# connections.net
KiCad netlist of a schematic drawn in EAGLE
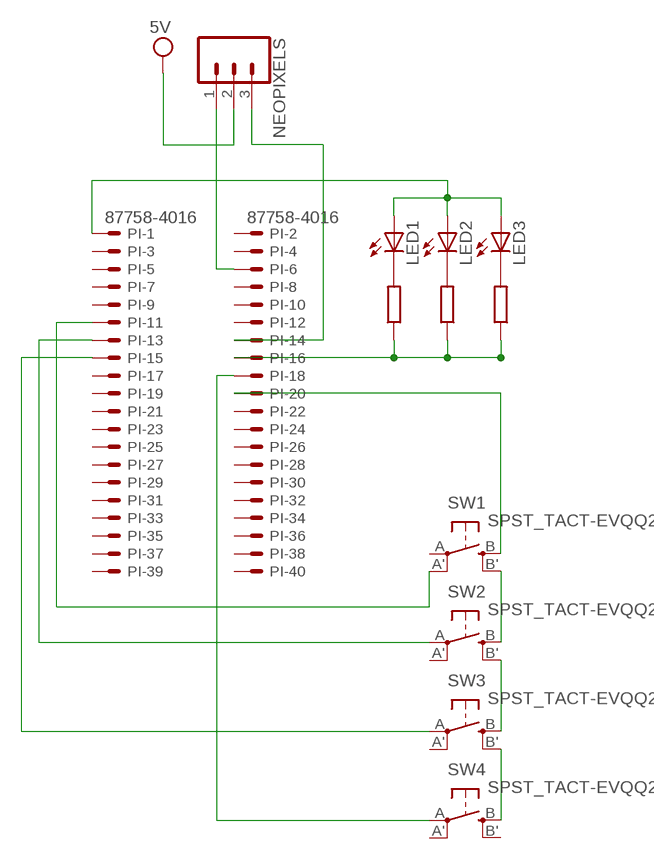
[diagram p0: schematic, sheet 1]

(export (version "E")
  (design (tool "Eeschema 10.0.6"))
  (components
    (comp (ref "LED1")
      (value "LED3MM")
      (footprint "eagle-import:LED3MM")
      (libsource (lib "eagle-import") (part "LED3MM"))
    )
    (comp (ref "LED2")
      (value "LED3MM")
      (footprint "eagle-import:LED3MM")
      (libsource (lib "eagle-import") (part "LED3MM"))
    )
    (comp (ref "LED3")
      (value "LED3MM")
      (footprint "eagle-import:LED3MM")
      (libsource (lib "eagle-import") (part "LED3MM"))
    )
    (comp (ref "NEOPIXELS")
      (value "CONN_031X03_NO_SILK")
      (footprint "eagle-import:1X03_NO_SILK")
      (libsource (lib "eagle-import") (part "CONN_031X03_NO_SILK"))
    )
    (comp (ref "PI")
      (value "87758-4016")
      (footprint "eagle-import:87758-4016")
      (fields (field (name "MF") "MOLEX"))
      (libsource (lib "eagle-import") (part "87758-4016"))
    )
    (comp (ref "SW1")
      (value "SPST_TACT-EVQQ2")
      (footprint "eagle-import:EVQ-Q2")
      (libsource (lib "eagle-import") (part "SPST_TACT-EVQQ2"))
    )
    (comp (ref "SW2")
      (value "SPST_TACT-EVQQ2")
      (footprint "eagle-import:EVQ-Q2")
      (libsource (lib "eagle-import") (part "SPST_TACT-EVQQ2"))
    )
    (comp (ref "SW3")
      (value "SPST_TACT-EVQQ2")
      (footprint "eagle-import:EVQ-Q2")
      (libsource (lib "eagle-import") (part "SPST_TACT-EVQQ2"))
    )
    (comp (ref "SW4")
      (value "SPST_TACT-EVQQ2")
      (footprint "eagle-import:EVQ-Q2")
      (libsource (lib "eagle-import") (part "SPST_TACT-EVQQ2"))
    )
  )
  (nets
    (net (code "1") (name "5V") (class "Default")
      (node (ref "NEOPIXELS") (pin "2") (pinfunction "2_2") (pintype "passive"))
    )
    (net (code "2") (name "Net-(PIA-S)") (class "Default")
      (node (ref "LED1") (pin "A") (pinfunction "A_A") (pintype "passive"))
      (node (ref "LED2") (pin "A") (pinfunction "A_A") (pintype "passive"))
      (node (ref "LED3") (pin "A") (pinfunction "A_A") (pintype "passive"))
      (node (ref "PI") (pin "1") (pinfunction "S_1") (pintype "passive"))
    )
    (net (code "3") (name "Net-(PIAK-S)") (class "Default")
      (node (ref "NEOPIXELS") (pin "1") (pinfunction "1_1") (pintype "passive"))
      (node (ref "PI") (pin "6") (pinfunction "S_6") (pintype "passive"))
    )
    (net (code "4") (name "Net-(PIC-S)") (class "Default")
      (node (ref "PI") (pin "11") (pinfunction "S_11") (pintype "passive"))
      (node (ref "SW1") (pin "A'") (pinfunction "P1_A'") (pintype "passive"))
    )
    (net (code "5") (name "Net-(PIE-S)") (class "Default")
      (node (ref "PI") (pin "13") (pinfunction "S_13") (pintype "passive"))
      (node (ref "SW2") (pin "A") (pinfunction "P_A") (pintype "passive"))
    )
    (net (code "6") (name "Net-(PIF-S)") (class "Default")
      (node (ref "NEOPIXELS") (pin "3") (pinfunction "3_3") (pintype "passive"))
      (node (ref "PI") (pin "14") (pinfunction "S_14") (pintype "passive"))
    )
    (net (code "7") (name "Net-(PIG-S)") (class "Default")
      (node (ref "PI") (pin "15") (pinfunction "S_15") (pintype "passive"))
      (node (ref "SW3") (pin "A") (pinfunction "P_A") (pintype "passive"))
    )
    (net (code "8") (name "Net-(PIJ-S)") (class "Default")
      (node (ref "PI") (pin "18") (pinfunction "S_18") (pintype "passive"))
      (node (ref "SW4") (pin "A") (pinfunction "P_A") (pintype "passive"))
    )
    (net (code "9") (name "Net-(PIM-S)") (class "Default")
      (node (ref "PI") (pin "20") (pinfunction "S_20") (pintype "passive"))
      (node (ref "SW1") (pin "B") (pinfunction "S_B") (pintype "passive"))
    )
    (net (code "10") (name "Net-(SW1-S1)") (class "Default")
      (node (ref "SW1") (pin "B'") (pinfunction "S1_B'") (pintype "passive"))
      (node (ref "SW2") (pin "B") (pinfunction "S_B") (pintype "passive"))
    )
    (net (code "11") (name "Net-(SW2-S1)") (class "Default")
      (node (ref "SW2") (pin "B'") (pinfunction "S1_B'") (pintype "passive"))
      (node (ref "SW3") (pin "B") (pinfunction "S_B") (pintype "passive"))
    )
    (net (code "12") (name "Net-(SW3-S1)") (class "Default")
      (node (ref "SW3") (pin "B'") (pinfunction "S1_B'") (pintype "passive"))
      (node (ref "SW4") (pin "B") (pinfunction "S_B") (pintype "passive"))
    )
    (net (code "13") (name "unconnected-(LED1-C-PadK)") (class "Default")
      (node (ref "LED1") (pin "K") (pinfunction "C_K") (pintype "passive"))
    )
    (net (code "14") (name "unconnected-(LED2-C-PadK)") (class "Default")
      (node (ref "LED2") (pin "K") (pinfunction "C_K") (pintype "passive"))
    )
    (net (code "15") (name "unconnected-(LED3-C-PadK)") (class "Default")
      (node (ref "LED3") (pin "K") (pinfunction "C_K") (pintype "passive"))
    )
    (net (code "16") (name "unconnected-(PIAA-S-Pad33)") (class "Default")
      (node (ref "PI") (pin "33") (pinfunction "S_33") (pintype "passive"))
    )
    (net (code "17") (name "unconnected-(PIAB-S-Pad34)") (class "Default")
      (node (ref "PI") (pin "34") (pinfunction "S_34") (pintype "passive"))
    )
    (net (code "18") (name "unconnected-(PIAC-S-Pad35)") (class "Default")
      (node (ref "PI") (pin "35") (pinfunction "S_35") (pintype "passive"))
    )
    (net (code "19") (name "unconnected-(PIAD-S-Pad36)") (class "Default")
      (node (ref "PI") (pin "36") (pinfunction "S_36") (pintype "passive"))
    )
    (net (code "20") (name "unconnected-(PIAE-S-Pad37)") (class "Default")
      (node (ref "PI") (pin "37") (pinfunction "S_37") (pintype "passive"))
    )
    (net (code "21") (name "unconnected-(PIAF-S-Pad38)") (class "Default")
      (node (ref "PI") (pin "38") (pinfunction "S_38") (pintype "passive"))
    )
    (net (code "22") (name "unconnected-(PIAG-S-Pad39)") (class "Default")
      (node (ref "PI") (pin "39") (pinfunction "S_39") (pintype "passive"))
    )
    (net (code "23") (name "unconnected-(PIAH-S-Pad4)") (class "Default")
      (node (ref "PI") (pin "4") (pinfunction "S_4") (pintype "passive"))
    )
    (net (code "24") (name "unconnected-(PIAI-S-Pad40)") (class "Default")
      (node (ref "PI") (pin "40") (pinfunction "S_40") (pintype "passive"))
    )
    (net (code "25") (name "unconnected-(PIAJ-S-Pad5)") (class "Default")
      (node (ref "PI") (pin "5") (pinfunction "S_5") (pintype "passive"))
    )
    (net (code "26") (name "unconnected-(PIAL-S-Pad7)") (class "Default")
      (node (ref "PI") (pin "7") (pinfunction "S_7") (pintype "passive"))
    )
    (net (code "27") (name "unconnected-(PIAM-S-Pad8)") (class "Default")
      (node (ref "PI") (pin "8") (pinfunction "S_8") (pintype "passive"))
    )
    (net (code "28") (name "unconnected-(PIAN-S-Pad9)") (class "Default")
      (node (ref "PI") (pin "9") (pinfunction "S_9") (pintype "passive"))
    )
    (net (code "29") (name "unconnected-(PIB-S-Pad10)") (class "Default")
      (node (ref "PI") (pin "10") (pinfunction "S_10") (pintype "passive"))
    )
    (net (code "30") (name "unconnected-(PID-S-Pad12)") (class "Default")
      (node (ref "PI") (pin "12") (pinfunction "S_12") (pintype "passive"))
    )
    (net (code "31") (name "unconnected-(PIH-S-Pad16)") (class "Default")
      (node (ref "PI") (pin "16") (pinfunction "S_16") (pintype "passive"))
    )
    (net (code "32") (name "unconnected-(PII-S-Pad17)") (class "Default")
      (node (ref "PI") (pin "17") (pinfunction "S_17") (pintype "passive"))
    )
    (net (code "33") (name "unconnected-(PIK-S-Pad19)") (class "Default")
      (node (ref "PI") (pin "19") (pinfunction "S_19") (pintype "passive"))
    )
    (net (code "34") (name "unconnected-(PIL-S-Pad2)") (class "Default")
      (node (ref "PI") (pin "2") (pinfunction "S_2") (pintype "passive"))
    )
    (net (code "35") (name "unconnected-(PIN-S-Pad21)") (class "Default")
      (node (ref "PI") (pin "21") (pinfunction "S_21") (pintype "passive"))
    )
    (net (code "36") (name "unconnected-(PIO-S-Pad22)") (class "Default")
      (node (ref "PI") (pin "22") (pinfunction "S_22") (pintype "passive"))
    )
    (net (code "37") (name "unconnected-(PIP-S-Pad23)") (class "Default")
      (node (ref "PI") (pin "23") (pinfunction "S_23") (pintype "passive"))
    )
    (net (code "38") (name "unconnected-(PIQ-S-Pad24)") (class "Default")
      (node (ref "PI") (pin "24") (pinfunction "S_24") (pintype "passive"))
    )
    (net (code "39") (name "unconnected-(PIR-S-Pad25)") (class "Default")
      (node (ref "PI") (pin "25") (pinfunction "S_25") (pintype "passive"))
    )
    (net (code "40") (name "unconnected-(PIS-S-Pad26)") (class "Default")
      (node (ref "PI") (pin "26") (pinfunction "S_26") (pintype "passive"))
    )
    (net (code "41") (name "unconnected-(PIT-S-Pad27)") (class "Default")
      (node (ref "PI") (pin "27") (pinfunction "S_27") (pintype "passive"))
    )
    (net (code "42") (name "unconnected-(PIU-S-Pad28)") (class "Default")
      (node (ref "PI") (pin "28") (pinfunction "S_28") (pintype "passive"))
    )
    (net (code "43") (name "unconnected-(PIV-S-Pad29)") (class "Default")
      (node (ref "PI") (pin "29") (pinfunction "S_29") (pintype "passive"))
    )
    (net (code "44") (name "unconnected-(PIW-S-Pad3)") (class "Default")
      (node (ref "PI") (pin "3") (pinfunction "S_3") (pintype "passive"))
    )
    (net (code "45") (name "unconnected-(PIX-S-Pad30)") (class "Default")
      (node (ref "PI") (pin "30") (pinfunction "S_30") (pintype "passive"))
    )
    (net (code "46") (name "unconnected-(PIY-S-Pad31)") (class "Default")
      (node (ref "PI") (pin "31") (pinfunction "S_31") (pintype "passive"))
    )
    (net (code "47") (name "unconnected-(PIZ-S-Pad32)") (class "Default")
      (node (ref "PI") (pin "32") (pinfunction "S_32") (pintype "passive"))
    )
    (net (code "48") (name "unconnected-(SW1-P-PadA)") (class "Default")
      (node (ref "SW1") (pin "A") (pinfunction "P_A") (pintype "passive"))
    )
    (net (code "49") (name "unconnected-(SW2-P1-PadA')") (class "Default")
      (node (ref "SW2") (pin "A'") (pinfunction "P1_A'") (pintype "passive"))
    )
    (net (code "50") (name "unconnected-(SW3-P1-PadA')") (class "Default")
      (node (ref "SW3") (pin "A'") (pinfunction "P1_A'") (pintype "passive"))
    )
    (net (code "51") (name "unconnected-(SW4-P1-PadA')") (class "Default")
      (node (ref "SW4") (pin "A'") (pinfunction "P1_A'") (pintype "passive"))
    )
    (net (code "52") (name "unconnected-(SW4-S1-PadB')") (class "Default")
      (node (ref "SW4") (pin "B'") (pinfunction "S1_B'") (pintype "passive"))
    )
  )
)
